# ESC-Player_KeyBoard_V04.net
KiCad netlist of a schematic drawn in EasyEDA Pro
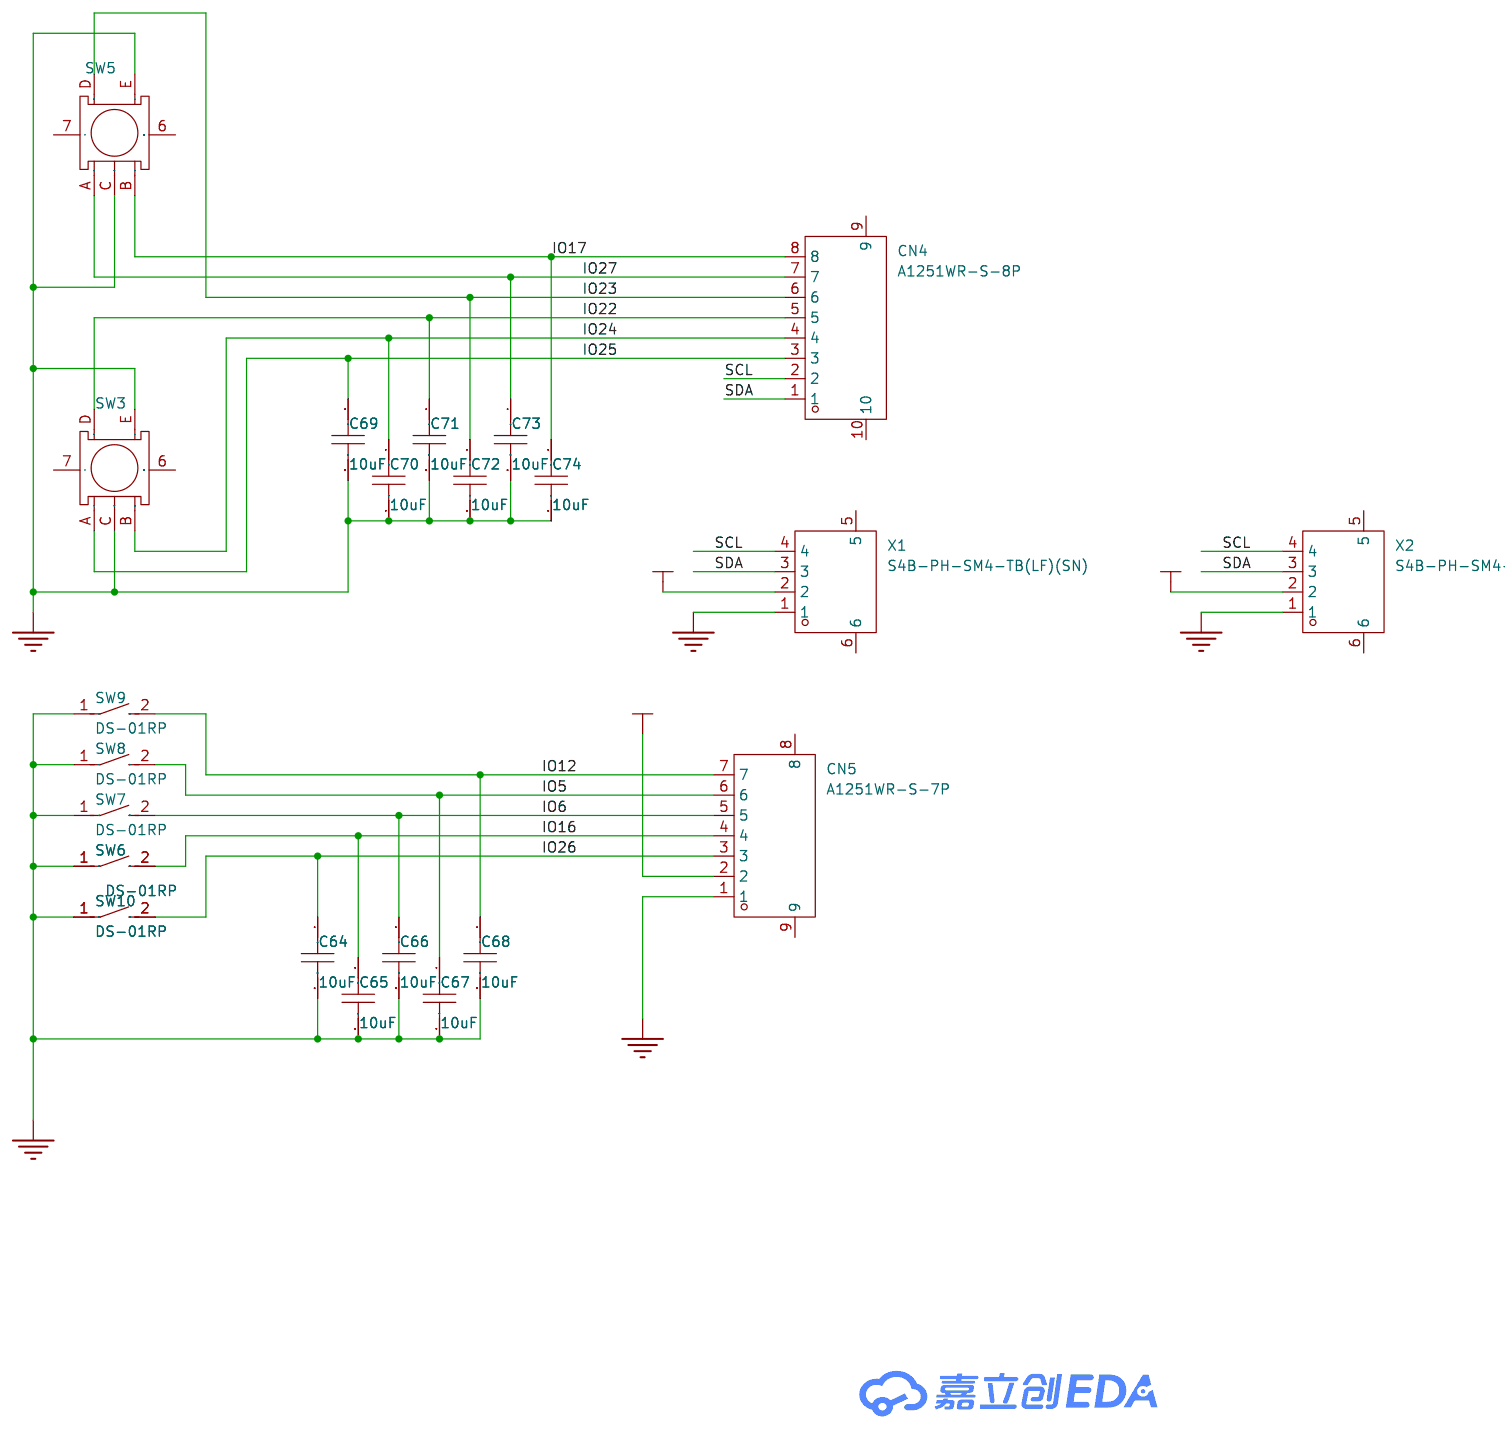
[diagram p0: schematic sheet]

(export (version "E")
  (design (tool "Eeschema 10.0.6"))
  (components
    (comp (ref "C64")
      (value "10uF")
      (footprint "easyedapro:C0805")
      (description "温度系数:X5R;额定电压:6.3V;精度:±10%;容值:10uF;")
      (fields
        (field (name "Manufacturer Part") "CL21A106KQFNNNE")
        (field (name "Manufacturer") "SAMSUNG(三星)")
      )
      (libsource (lib "easyedapro") (part "CL21A106KQFNNNE"))
    )
    (comp (ref "C65")
      (value "10uF")
      (footprint "easyedapro:C0805")
      (description "温度系数:X5R;额定电压:6.3V;精度:±10%;容值:10uF;")
      (fields
        (field (name "Manufacturer Part") "CL21A106KQFNNNE")
        (field (name "Manufacturer") "SAMSUNG(三星)")
      )
      (libsource (lib "easyedapro") (part "CL21A106KQFNNNE"))
    )
    (comp (ref "C66")
      (value "10uF")
      (footprint "easyedapro:C0805")
      (description "温度系数:X5R;额定电压:6.3V;精度:±10%;容值:10uF;")
      (fields
        (field (name "Manufacturer Part") "CL21A106KQFNNNE")
        (field (name "Manufacturer") "SAMSUNG(三星)")
      )
      (libsource (lib "easyedapro") (part "CL21A106KQFNNNE"))
    )
    (comp (ref "C67")
      (value "10uF")
      (footprint "easyedapro:C0805")
      (description "温度系数:X5R;额定电压:6.3V;精度:±10%;容值:10uF;")
      (fields
        (field (name "Manufacturer Part") "CL21A106KQFNNNE")
        (field (name "Manufacturer") "SAMSUNG(三星)")
      )
      (libsource (lib "easyedapro") (part "CL21A106KQFNNNE"))
    )
    (comp (ref "C68")
      (value "10uF")
      (footprint "easyedapro:C0805")
      (description "温度系数:X5R;额定电压:6.3V;精度:±10%;容值:10uF;")
      (fields
        (field (name "Manufacturer Part") "CL21A106KQFNNNE")
        (field (name "Manufacturer") "SAMSUNG(三星)")
      )
      (libsource (lib "easyedapro") (part "CL21A106KQFNNNE"))
    )
    (comp (ref "C69")
      (value "10uF")
      (footprint "easyedapro:C0805")
      (description "温度系数:X5R;额定电压:6.3V;精度:±10%;容值:10uF;")
      (fields
        (field (name "Manufacturer Part") "CL21A106KQFNNNE")
        (field (name "Manufacturer") "SAMSUNG(三星)")
      )
      (libsource (lib "easyedapro") (part "CL21A106KQFNNNE"))
    )
    (comp (ref "C70")
      (value "10uF")
      (footprint "easyedapro:C0805")
      (description "温度系数:X5R;额定电压:6.3V;精度:±10%;容值:10uF;")
      (fields
        (field (name "Manufacturer Part") "CL21A106KQFNNNE")
        (field (name "Manufacturer") "SAMSUNG(三星)")
      )
      (libsource (lib "easyedapro") (part "CL21A106KQFNNNE"))
    )
    (comp (ref "C71")
      (value "10uF")
      (footprint "easyedapro:C0805")
      (description "温度系数:X5R;额定电压:6.3V;精度:±10%;容值:10uF;")
      (fields
        (field (name "Manufacturer Part") "CL21A106KQFNNNE")
        (field (name "Manufacturer") "SAMSUNG(三星)")
      )
      (libsource (lib "easyedapro") (part "CL21A106KQFNNNE"))
    )
    (comp (ref "C72")
      (value "10uF")
      (footprint "easyedapro:C0805")
      (description "温度系数:X5R;额定电压:6.3V;精度:±10%;容值:10uF;")
      (fields
        (field (name "Manufacturer Part") "CL21A106KQFNNNE")
        (field (name "Manufacturer") "SAMSUNG(三星)")
      )
      (libsource (lib "easyedapro") (part "CL21A106KQFNNNE"))
    )
    (comp (ref "C73")
      (value "10uF")
      (footprint "easyedapro:C0805")
      (description "温度系数:X5R;额定电压:6.3V;精度:±10%;容值:10uF;")
      (fields
        (field (name "Manufacturer Part") "CL21A106KQFNNNE")
        (field (name "Manufacturer") "SAMSUNG(三星)")
      )
      (libsource (lib "easyedapro") (part "CL21A106KQFNNNE"))
    )
    (comp (ref "C74")
      (value "10uF")
      (footprint "easyedapro:C0805")
      (description "温度系数:X5R;额定电压:6.3V;精度:±10%;容值:10uF;")
      (fields
        (field (name "Manufacturer Part") "CL21A106KQFNNNE")
        (field (name "Manufacturer") "SAMSUNG(三星)")
      )
      (libsource (lib "easyedapro") (part "CL21A106KQFNNNE"))
    )
    (comp (ref "CN4")
      (value "A1251WR-S-8P")
      (footprint "easyedapro:CONN-SMD_A1251WR-S-8P")
      (description "参考系列:-;间距:1.25mm;插针结构:1x8P;排数:1;每排PIN数:8;行距:-;安装方式:-;触头材质:磷青铜;")
      (fields (field (name "Manufacturer") "CJT(长江连接器)"))
      (libsource (lib "easyedapro") (part "A1251WR-S-8P"))
    )
    (comp (ref "CN5")
      (value "A1251WR-S-7P")
      (footprint "easyedapro:CONN-SMD_A1251WR-S-7P")
      (description "参考系列:-;间距:1.25mm;插针结构:1x7P;排数:1;每排PIN数:7;行距:-;安装方式:-;触头材质:磷青铜;")
      (fields (field (name "Manufacturer") "CJT(长江连接器)"))
      (libsource (lib "easyedapro") (part "A1251WR-S-7P"))
    )
    (comp (ref "SW3")
      (value "~")
      (footprint "easyedapro:旋转编码器")
      (libsource (lib "easyedapro") (part "旋转编码器"))
    )
    (comp (ref "SW5")
      (value "~")
      (footprint "easyedapro:旋转编码器")
      (libsource (lib "easyedapro") (part "旋转编码器"))
    )
    (comp (ref "SW6")
      (value "DS-01RP")
      (footprint "easyedapro:SW-TH_DS-01RP")
      (description "类型:平拨，凸起式;额定电流:25mA;额定电压:24V;电路结构:单刀单掷;开关位数:1;引脚间距:-;工作温度:-20°C~+70°C;使用寿命:3000;颜色:红色;")
      (fields (field (name "Manufacturer") "韩国韩荣"))
      (libsource (lib "easyedapro") (part "DS-01RP"))
    )
    (comp (ref "SW7")
      (value "DS-01RP")
      (footprint "easyedapro:SW-TH_DS-01RP")
      (description "类型:平拨，凸起式;额定电流:25mA;额定电压:24V;电路结构:单刀单掷;开关位数:1;引脚间距:-;工作温度:-20°C~+70°C;使用寿命:3000;颜色:红色;")
      (fields (field (name "Manufacturer") "韩国韩荣"))
      (libsource (lib "easyedapro") (part "DS-01RP"))
    )
    (comp (ref "SW8")
      (value "DS-01RP")
      (footprint "easyedapro:SW-TH_DS-01RP")
      (description "类型:平拨，凸起式;额定电流:25mA;额定电压:24V;电路结构:单刀单掷;开关位数:1;引脚间距:-;工作温度:-20°C~+70°C;使用寿命:3000;颜色:红色;")
      (fields (field (name "Manufacturer") "韩国韩荣"))
      (libsource (lib "easyedapro") (part "DS-01RP"))
    )
    (comp (ref "SW9")
      (value "DS-01RP")
      (footprint "easyedapro:SW-TH_DS-01RP")
      (description "类型:平拨，凸起式;额定电流:25mA;额定电压:24V;电路结构:单刀单掷;开关位数:1;引脚间距:-;工作温度:-20°C~+70°C;使用寿命:3000;颜色:红色;")
      (fields (field (name "Manufacturer") "韩国韩荣"))
      (libsource (lib "easyedapro") (part "DS-01RP"))
    )
    (comp (ref "SW10")
      (value "DS-01RP")
      (footprint "easyedapro:SW-TH_DS-01RP")
      (description "类型:平拨，凸起式;额定电流:25mA;额定电压:24V;电路结构:单刀单掷;开关位数:1;引脚间距:-;工作温度:-20°C~+70°C;使用寿命:3000;颜色:红色;")
      (fields (field (name "Manufacturer") "韩国韩荣"))
      (libsource (lib "easyedapro") (part "DS-01RP"))
    )
    (comp (ref "X1")
      (value "S4B-PH-SM4-TB(LF)(SN)")
      (footprint "easyedapro:CONN-SMD_S4B-PH-SM4-TB-LF-SN")
      (description "参考系列:PH;间距:2mm;插针结构:1x4P;排数:1;每排PIN数:4;行距:-;安装方式:-;触头材质:铜合金;")
      (fields (field (name "Manufacturer") "JST"))
      (libsource (lib "easyedapro") (part "S4B-PH-SM4-TB(LF)(SN)"))
    )
    (comp (ref "X2")
      (value "S4B-PH-SM4-TB(LF)(SN)")
      (footprint "easyedapro:CONN-SMD_S4B-PH-SM4-TB-LF-SN")
      (description "参考系列:PH;间距:2mm;插针结构:1x4P;排数:1;每排PIN数:4;行距:-;安装方式:-;触头材质:铜合金;")
      (fields (field (name "Manufacturer") "JST"))
      (libsource (lib "easyedapro") (part "S4B-PH-SM4-TB(LF)(SN)"))
    )
  )
  (nets
    (net (code "1") (name "/IO5") (class "Default")
      (node (ref "C67") (pin "1") (pinfunction "1_1") (pintype "input"))
      (node (ref "CN5") (pin "6") (pinfunction "6_6") (pintype "input"))
      (node (ref "SW8") (pin "2") (pinfunction "2_2") (pintype "input"))
    )
    (net (code "2") (name "/IO6") (class "Default")
      (node (ref "C66") (pin "1") (pinfunction "1_1") (pintype "input"))
      (node (ref "CN5") (pin "5") (pinfunction "5_5") (pintype "input"))
      (node (ref "SW7") (pin "2") (pinfunction "2_2") (pintype "input"))
    )
    (net (code "3") (name "/IO12") (class "Default")
      (node (ref "C68") (pin "1") (pinfunction "1_1") (pintype "input"))
      (node (ref "CN5") (pin "7") (pinfunction "7_7") (pintype "input"))
      (node (ref "SW9") (pin "2") (pinfunction "2_2") (pintype "input"))
    )
    (net (code "4") (name "/IO16") (class "Default")
      (node (ref "C65") (pin "1") (pinfunction "1_1") (pintype "input"))
      (node (ref "CN5") (pin "4") (pinfunction "4_4") (pintype "input"))
      (node (ref "SW6") (pin "2") (pinfunction "2_2") (pintype "input"))
    )
    (net (code "5") (name "/IO17") (class "Default")
      (node (ref "C74") (pin "1") (pinfunction "1_1") (pintype "input"))
      (node (ref "CN4") (pin "8") (pinfunction "8_8") (pintype "input"))
      (node (ref "SW5") (pin "B") (pinfunction "B_B") (pintype "input"))
    )
    (net (code "6") (name "/IO22") (class "Default")
      (node (ref "C71") (pin "1") (pinfunction "1_1") (pintype "input"))
      (node (ref "CN4") (pin "5") (pinfunction "5_5") (pintype "input"))
      (node (ref "SW3") (pin "D") (pinfunction "D_D") (pintype "input"))
    )
    (net (code "7") (name "/IO23") (class "Default")
      (node (ref "C72") (pin "1") (pinfunction "1_1") (pintype "input"))
      (node (ref "CN4") (pin "6") (pinfunction "6_6") (pintype "input"))
      (node (ref "SW5") (pin "D") (pinfunction "D_D") (pintype "input"))
    )
    (net (code "8") (name "/IO24") (class "Default")
      (node (ref "C70") (pin "1") (pinfunction "1_1") (pintype "input"))
      (node (ref "CN4") (pin "4") (pinfunction "4_4") (pintype "input"))
      (node (ref "SW3") (pin "B") (pinfunction "B_B") (pintype "input"))
    )
    (net (code "9") (name "/IO25") (class "Default")
      (node (ref "C69") (pin "1") (pinfunction "1_1") (pintype "input"))
      (node (ref "CN4") (pin "3") (pinfunction "3_3") (pintype "input"))
      (node (ref "SW3") (pin "A") (pinfunction "A_A") (pintype "input"))
    )
    (net (code "10") (name "/IO26") (class "Default")
      (node (ref "C64") (pin "1") (pinfunction "1_1") (pintype "input"))
      (node (ref "CN5") (pin "3") (pinfunction "3_3") (pintype "input"))
      (node (ref "SW10") (pin "2") (pinfunction "2_2") (pintype "input"))
    )
    (net (code "11") (name "/IO27") (class "Default")
      (node (ref "C73") (pin "1") (pinfunction "1_1") (pintype "input"))
      (node (ref "CN4") (pin "7") (pinfunction "7_7") (pintype "input"))
      (node (ref "SW5") (pin "A") (pinfunction "A_A") (pintype "input"))
    )
    (net (code "12") (name "/SCL") (class "Default")
      (node (ref "CN4") (pin "2") (pinfunction "2_2") (pintype "input"))
      (node (ref "X1") (pin "4") (pinfunction "4_4") (pintype "input"))
      (node (ref "X2") (pin "4") (pinfunction "4_4") (pintype "input"))
    )
    (net (code "13") (name "/SDA") (class "Default")
      (node (ref "CN4") (pin "1") (pinfunction "1_1") (pintype "input"))
      (node (ref "X1") (pin "3") (pinfunction "3_3") (pintype "input"))
      (node (ref "X2") (pin "3") (pinfunction "3_3") (pintype "input"))
    )
    (net (code "14") (name "5V") (class "Default")
      (node (ref "CN5") (pin "2") (pinfunction "2_2") (pintype "input"))
      (node (ref "X1") (pin "2") (pinfunction "2_2") (pintype "input"))
      (node (ref "X2") (pin "2") (pinfunction "2_2") (pintype "input"))
    )
    (net (code "15") (name "GND") (class "Default")
      (node (ref "C64") (pin "2") (pinfunction "2_2") (pintype "input"))
      (node (ref "C65") (pin "2") (pinfunction "2_2") (pintype "input"))
      (node (ref "C66") (pin "2") (pinfunction "2_2") (pintype "input"))
      (node (ref "C67") (pin "2") (pinfunction "2_2") (pintype "input"))
      (node (ref "C68") (pin "2") (pinfunction "2_2") (pintype "input"))
      (node (ref "C69") (pin "2") (pinfunction "2_2") (pintype "input"))
      (node (ref "C70") (pin "2") (pinfunction "2_2") (pintype "input"))
      (node (ref "C71") (pin "2") (pinfunction "2_2") (pintype "input"))
      (node (ref "C72") (pin "2") (pinfunction "2_2") (pintype "input"))
      (node (ref "C73") (pin "2") (pinfunction "2_2") (pintype "input"))
      (node (ref "C74") (pin "2") (pinfunction "2_2") (pintype "input"))
      (node (ref "CN5") (pin "1") (pinfunction "1_1") (pintype "input"))
      (node (ref "SW10") (pin "1") (pinfunction "1_1") (pintype "input"))
      (node (ref "SW3") (pin "C") (pinfunction "C_C") (pintype "input"))
      (node (ref "SW3") (pin "E") (pinfunction "E_E") (pintype "input"))
      (node (ref "SW5") (pin "C") (pinfunction "C_C") (pintype "input"))
      (node (ref "SW5") (pin "E") (pinfunction "E_E") (pintype "input"))
      (node (ref "SW6") (pin "1") (pinfunction "1_1") (pintype "input"))
      (node (ref "SW7") (pin "1") (pinfunction "1_1") (pintype "input"))
      (node (ref "SW8") (pin "1") (pinfunction "1_1") (pintype "input"))
      (node (ref "SW9") (pin "1") (pinfunction "1_1") (pintype "input"))
      (node (ref "X1") (pin "1") (pinfunction "1_1") (pintype "input"))
      (node (ref "X2") (pin "1") (pinfunction "1_1") (pintype "input"))
    )
    (net (code "16") (name "unconnected-(CN4-Pad9)") (class "Default")
      (node (ref "CN4") (pin "9") (pinfunction "9_9") (pintype "input"))
    )
    (net (code "17") (name "unconnected-(CN4-Pad10)") (class "Default")
      (node (ref "CN4") (pin "10") (pinfunction "10_10") (pintype "input"))
    )
    (net (code "18") (name "unconnected-(CN5-Pad8)") (class "Default")
      (node (ref "CN5") (pin "8") (pinfunction "8_8") (pintype "input"))
    )
    (net (code "19") (name "unconnected-(CN5-Pad9)") (class "Default")
      (node (ref "CN5") (pin "9") (pinfunction "9_9") (pintype "input"))
    )
    (net (code "20") (name "unconnected-(SW3-Pad6)") (class "Default")
      (node (ref "SW3") (pin "6") (pinfunction "6_6") (pintype "input"))
    )
    (net (code "21") (name "unconnected-(SW3-Pad7)") (class "Default")
      (node (ref "SW3") (pin "7") (pinfunction "7_7") (pintype "input"))
    )
    (net (code "22") (name "unconnected-(SW5-Pad6)") (class "Default")
      (node (ref "SW5") (pin "6") (pinfunction "6_6") (pintype "input"))
    )
    (net (code "23") (name "unconnected-(SW5-Pad7)") (class "Default")
      (node (ref "SW5") (pin "7") (pinfunction "7_7") (pintype "input"))
    )
    (net (code "24") (name "unconnected-(X1-Pad5)") (class "Default")
      (node (ref "X1") (pin "5") (pinfunction "5_5") (pintype "input"))
    )
    (net (code "25") (name "unconnected-(X1-Pad6)") (class "Default")
      (node (ref "X1") (pin "6") (pinfunction "6_6") (pintype "input"))
    )
    (net (code "26") (name "unconnected-(X2-Pad5)") (class "Default")
      (node (ref "X2") (pin "5") (pinfunction "5_5") (pintype "input"))
    )
    (net (code "27") (name "unconnected-(X2-Pad6)") (class "Default")
      (node (ref "X2") (pin "6") (pinfunction "6_6") (pintype "input"))
    )
  )
)
